# Connectors.net
KiCad netlist of a schematic drawn in Altium Designer
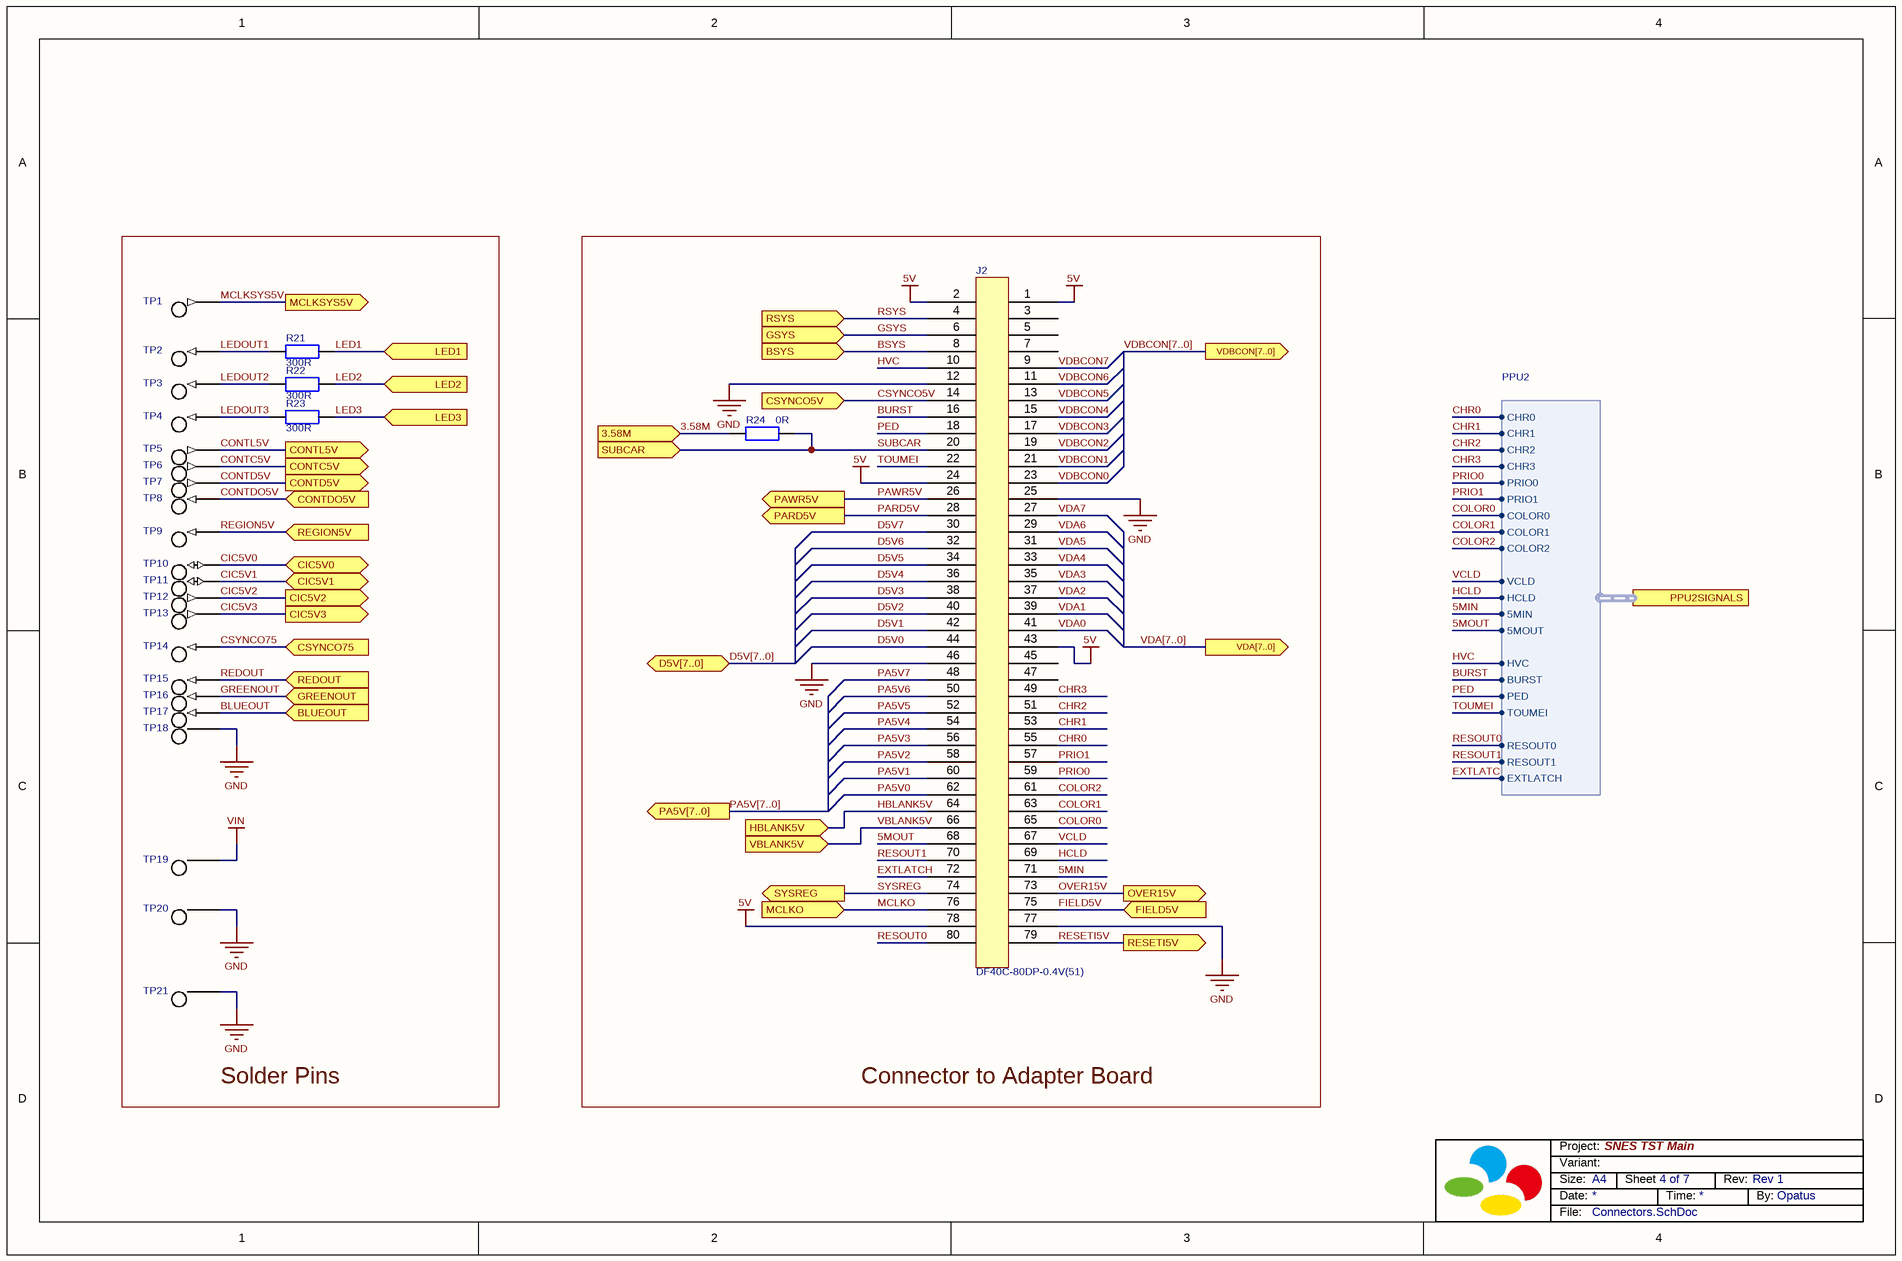
[diagram p0: Connectors.SchDoc]

(export (version "E")
  (design (tool "Eeschema 10.0.6"))
  (components
    (comp (ref "J2")
      (value "DF40C-80DP")
      (footprint "DF40C-80DP")
      (description "80Pole Connector")
      (fields
        (field (name "MANUFACTURER_PART_NUMBER") "DF40C-80DP-0.4V(51)")
        (field (name "MANUFACTURER") "Hirose Connector")
      )
      (libsource (lib "PCB") (part "Conn 80P"))
    )
    (comp (ref "R21")
      (value "300R")
      (footprint "Res_0603_Chip")
      (fields (field (name "TOLERANCE") "±1%") (field (name "Comment") "Resistor 300R 0603 ±1%"))
      (libsource (lib "PCB") (part "R"))
    )
    (comp (ref "R22")
      (value "300R")
      (footprint "Res_0603_Chip")
      (fields (field (name "TOLERANCE") "±1%") (field (name "Comment") "Resistor 300R 0603 ±1%"))
      (libsource (lib "PCB") (part "R"))
    )
    (comp (ref "R23")
      (value "300R")
      (footprint "Res_0603_Chip")
      (fields (field (name "TOLERANCE") "±1%") (field (name "Comment") "Resistor 300R 0603 ±1%"))
      (libsource (lib "PCB") (part "R"))
    )
    (comp (ref "R24")
      (value "0R")
      (footprint "Res_0603_Chip")
      (fields (field (name "TOLERANCE") "±1%") (field (name "Comment") "Resistor 0R 0603 ±1%"))
      (libsource (lib "") (part "R_1"))
    )
    (comp (ref "TP1")
      (value "Pin Connector")
      (footprint "Pin Connector Small")
      (libsource (lib "PCB") (part "Pin Connector"))
    )
    (comp (ref "TP2")
      (value "Pin Connector")
      (footprint "Pin Connector Small")
      (libsource (lib "PCB") (part "Pin Connector"))
    )
    (comp (ref "TP3")
      (value "Pin Connector")
      (footprint "Pin Connector Small")
      (libsource (lib "PCB") (part "Pin Connector"))
    )
    (comp (ref "TP4")
      (value "Pin Connector")
      (footprint "Pin Connector Small")
      (libsource (lib "PCB") (part "Pin Connector"))
    )
    (comp (ref "TP5")
      (value "Pin Connector")
      (footprint "Pin Connector Small")
      (libsource (lib "PCB") (part "Pin Connector"))
    )
    (comp (ref "TP6")
      (value "Pin Connector")
      (footprint "Pin Connector Small")
      (libsource (lib "PCB") (part "Pin Connector"))
    )
    (comp (ref "TP7")
      (value "Pin Connector")
      (footprint "Pin Connector Small")
      (libsource (lib "PCB") (part "Pin Connector"))
    )
    (comp (ref "TP8")
      (value "Pin Connector")
      (footprint "Pin Connector Small")
      (libsource (lib "PCB") (part "Pin Connector"))
    )
    (comp (ref "TP9")
      (value "Pin Connector")
      (footprint "Pin Connector Small")
      (libsource (lib "PCB") (part "Pin Connector"))
    )
    (comp (ref "TP10")
      (value "Pin Connector")
      (footprint "Pin Connector Small")
      (libsource (lib "PCB") (part "Pin Connector"))
    )
    (comp (ref "TP11")
      (value "Pin Connector")
      (footprint "Pin Connector Small")
      (libsource (lib "PCB") (part "Pin Connector"))
    )
    (comp (ref "TP12")
      (value "Pin Connector")
      (footprint "Pin Connector Small")
      (libsource (lib "PCB") (part "Pin Connector"))
    )
    (comp (ref "TP13")
      (value "Pin Connector")
      (footprint "Pin Connector Small")
      (libsource (lib "PCB") (part "Pin Connector"))
    )
    (comp (ref "TP14")
      (value "Pin Connector")
      (footprint "Pin Connector Small")
      (libsource (lib "PCB") (part "Pin Connector"))
    )
    (comp (ref "TP15")
      (value "Pin Connector")
      (footprint "Pin Connector Small")
      (libsource (lib "PCB") (part "Pin Connector"))
    )
    (comp (ref "TP16")
      (value "Pin Connector")
      (footprint "Pin Connector Small")
      (libsource (lib "PCB") (part "Pin Connector"))
    )
    (comp (ref "TP17")
      (value "Pin Connector")
      (footprint "Pin Connector Small")
      (libsource (lib "PCB") (part "Pin Connector"))
    )
    (comp (ref "TP18")
      (value "Pin Connector")
      (footprint "Pin Connector Small")
      (libsource (lib "PCB") (part "Pin Connector"))
    )
    (comp (ref "TP19")
      (value "Pin Connector")
      (footprint "Pin Connector Small")
      (libsource (lib "PCB") (part "Pin Connector"))
    )
    (comp (ref "TP20")
      (value "Pin Connector")
      (footprint "Pin Connector Small")
      (libsource (lib "PCB") (part "Pin Connector"))
    )
    (comp (ref "TP21")
      (value "Pin Connector")
      (footprint "Pin Connector Small")
      (libsource (lib "PCB") (part "Pin Connector"))
    )
  )
  (nets
    (net (code "2") (name "/3.58M") (class "Default") (node (ref "R24") (pin "2") (pintype "passive")))
    (net (code "3") (name "/5MIN") (class "Default") (node (ref "J2") (pin "71") (pintype "passive")))
    (net (code "4") (name "/5MOUT") (class "Default") (node (ref "J2") (pin "68") (pintype "passive")))
    (net (code "5") (name "/BLUEOUT") (class "Default")
      (node (ref "TP17") (pin "1") (pinfunction "0_1") (pintype "output"))
    )
    (net (code "6") (name "/BSYS") (class "Default") (node (ref "J2") (pin "8") (pintype "passive")))
    (net (code "7") (name "/BURST") (class "Default") (node (ref "J2") (pin "16") (pintype "passive")))
    (net (code "8") (name "/CHR0") (class "Default") (node (ref "J2") (pin "55") (pintype "passive")))
    (net (code "9") (name "/CHR1") (class "Default") (node (ref "J2") (pin "53") (pintype "passive")))
    (net (code "10") (name "/CHR2") (class "Default") (node (ref "J2") (pin "51") (pintype "passive")))
    (net (code "11") (name "/CHR3") (class "Default") (node (ref "J2") (pin "49") (pintype "passive")))
    (net (code "12") (name "/CIC5V0") (class "Default")
      (node (ref "TP10") (pin "1") (pinfunction "0_1") (pintype "output"))
    )
    (net (code "13") (name "/CIC5V1") (class "Default")
      (node (ref "TP11") (pin "1") (pinfunction "0_1") (pintype "output"))
    )
    (net (code "14") (name "/CIC5V2") (class "Default")
      (node (ref "TP12") (pin "1") (pinfunction "0_1") (pintype "output"))
    )
    (net (code "15") (name "/CIC5V3") (class "Default")
      (node (ref "TP13") (pin "1") (pinfunction "0_1") (pintype "output"))
    )
    (net (code "16") (name "/COLOR0") (class "Default") (node (ref "J2") (pin "65") (pintype "passive")))
    (net (code "17") (name "/COLOR1") (class "Default") (node (ref "J2") (pin "63") (pintype "passive")))
    (net (code "18") (name "/COLOR2") (class "Default") (node (ref "J2") (pin "61") (pintype "passive")))
    (net (code "19") (name "/CONTC5V") (class "Default")
      (node (ref "TP6") (pin "1") (pinfunction "0_1") (pintype "output"))
    )
    (net (code "20") (name "/CONTD5V") (class "Default")
      (node (ref "TP7") (pin "1") (pinfunction "0_1") (pintype "output"))
    )
    (net (code "21") (name "/CONTDO5V") (class "Default")
      (node (ref "TP8") (pin "1") (pinfunction "0_1") (pintype "output"))
    )
    (net (code "22") (name "/CONTL5V") (class "Default")
      (node (ref "TP5") (pin "1") (pinfunction "0_1") (pintype "output"))
    )
    (net (code "23") (name "/CSYNCO5V") (class "Default") (node (ref "J2") (pin "14") (pintype "passive")))
    (net (code "24") (name "/CSYNCO75") (class "Default")
      (node (ref "TP14") (pin "1") (pinfunction "0_1") (pintype "output"))
    )
    (net (code "25") (name "/D5V0") (class "Default") (node (ref "J2") (pin "44") (pintype "passive")))
    (net (code "26") (name "/D5V1") (class "Default") (node (ref "J2") (pin "42") (pintype "passive")))
    (net (code "27") (name "/D5V2") (class "Default") (node (ref "J2") (pin "40") (pintype "passive")))
    (net (code "28") (name "/D5V3") (class "Default") (node (ref "J2") (pin "38") (pintype "passive")))
    (net (code "29") (name "/D5V4") (class "Default") (node (ref "J2") (pin "36") (pintype "passive")))
    (net (code "30") (name "/D5V5") (class "Default") (node (ref "J2") (pin "34") (pintype "passive")))
    (net (code "31") (name "/D5V6") (class "Default") (node (ref "J2") (pin "32") (pintype "passive")))
    (net (code "32") (name "/D5V7") (class "Default") (node (ref "J2") (pin "30") (pintype "passive")))
    (net (code "34") (name "/EXTLATCH") (class "Default") (node (ref "J2") (pin "72") (pintype "passive")))
    (net (code "35") (name "/FIELD5V") (class "Default") (node (ref "J2") (pin "75") (pintype "passive")))
    (net (code "36") (name "/GREENOUT") (class "Default")
      (node (ref "TP16") (pin "1") (pinfunction "0_1") (pintype "output"))
    )
    (net (code "37") (name "/GSYS") (class "Default") (node (ref "J2") (pin "6") (pintype "passive")))
    (net (code "38") (name "/HBLANK5V") (class "Default") (node (ref "J2") (pin "64") (pintype "passive")))
    (net (code "39") (name "/HCLD") (class "Default") (node (ref "J2") (pin "69") (pintype "passive")))
    (net (code "40") (name "/HVC") (class "Default") (node (ref "J2") (pin "10") (pintype "passive")))
    (net (code "41") (name "/LED1") (class "Default") (node (ref "R21") (pin "2") (pintype "passive")))
    (net (code "42") (name "/LED2") (class "Default") (node (ref "R22") (pin "2") (pintype "passive")))
    (net (code "43") (name "/LED3") (class "Default") (node (ref "R23") (pin "2") (pintype "passive")))
    (net (code "44") (name "/LEDOUT1") (class "Default")
      (node (ref "R21") (pin "1") (pintype "passive"))
      (node (ref "TP2") (pin "1") (pinfunction "0_1") (pintype "output"))
    )
    (net (code "45") (name "/LEDOUT2") (class "Default")
      (node (ref "R22") (pin "1") (pintype "passive"))
      (node (ref "TP3") (pin "1") (pinfunction "0_1") (pintype "output"))
    )
    (net (code "46") (name "/LEDOUT3") (class "Default")
      (node (ref "R23") (pin "1") (pintype "passive"))
      (node (ref "TP4") (pin "1") (pinfunction "0_1") (pintype "output"))
    )
    (net (code "47") (name "/MCLKO") (class "Default") (node (ref "J2") (pin "76") (pintype "passive")))
    (net (code "48") (name "/MCLKSYS5V") (class "Default")
      (node (ref "TP1") (pin "1") (pinfunction "0_1") (pintype "output"))
    )
    (net (code "49") (name "/OVER15V") (class "Default") (node (ref "J2") (pin "73") (pintype "passive")))
    (net (code "50") (name "/PA5V0") (class "Default") (node (ref "J2") (pin "62") (pintype "passive")))
    (net (code "51") (name "/PA5V1") (class "Default") (node (ref "J2") (pin "60") (pintype "passive")))
    (net (code "52") (name "/PA5V2") (class "Default") (node (ref "J2") (pin "58") (pintype "passive")))
    (net (code "53") (name "/PA5V3") (class "Default") (node (ref "J2") (pin "56") (pintype "passive")))
    (net (code "54") (name "/PA5V4") (class "Default") (node (ref "J2") (pin "54") (pintype "passive")))
    (net (code "55") (name "/PA5V5") (class "Default") (node (ref "J2") (pin "52") (pintype "passive")))
    (net (code "56") (name "/PA5V6") (class "Default") (node (ref "J2") (pin "50") (pintype "passive")))
    (net (code "57") (name "/PA5V7") (class "Default") (node (ref "J2") (pin "48") (pintype "passive")))
    (net (code "59") (name "/PARD5V") (class "Default") (node (ref "J2") (pin "28") (pintype "passive")))
    (net (code "60") (name "/PAWR5V") (class "Default") (node (ref "J2") (pin "26") (pintype "passive")))
    (net (code "61") (name "/PED") (class "Default") (node (ref "J2") (pin "18") (pintype "passive")))
    (net (code "62") (name "/PRIO0") (class "Default") (node (ref "J2") (pin "59") (pintype "passive")))
    (net (code "63") (name "/PRIO1") (class "Default") (node (ref "J2") (pin "57") (pintype "passive")))
    (net (code "64") (name "/REDOUT") (class "Default")
      (node (ref "TP15") (pin "1") (pinfunction "0_1") (pintype "output"))
    )
    (net (code "65") (name "/REGION5V") (class "Default")
      (node (ref "TP9") (pin "1") (pinfunction "0_1") (pintype "output"))
    )
    (net (code "66") (name "/RESETI5V") (class "Default") (node (ref "J2") (pin "79") (pintype "passive")))
    (net (code "67") (name "/RESOUT0") (class "Default") (node (ref "J2") (pin "80") (pintype "passive")))
    (net (code "68") (name "/RESOUT1") (class "Default") (node (ref "J2") (pin "70") (pintype "passive")))
    (net (code "69") (name "/RSYS") (class "Default") (node (ref "J2") (pin "4") (pintype "passive")))
    (net (code "70") (name "/SUBCAR") (class "Default")
      (node (ref "J2") (pin "20") (pintype "passive"))
      (node (ref "R24") (pin "1") (pintype "passive"))
    )
    (net (code "71") (name "/SYSREG") (class "Default") (node (ref "J2") (pin "74") (pintype "passive")))
    (net (code "72") (name "/TOUMEI") (class "Default") (node (ref "J2") (pin "22") (pintype "passive")))
    (net (code "73") (name "/VBLANK5V") (class "Default") (node (ref "J2") (pin "66") (pintype "passive")))
    (net (code "74") (name "/VCLD") (class "Default") (node (ref "J2") (pin "67") (pintype "passive")))
    (net (code "75") (name "/VDA0") (class "Default") (node (ref "J2") (pin "41") (pintype "passive")))
    (net (code "76") (name "/VDA1") (class "Default") (node (ref "J2") (pin "39") (pintype "passive")))
    (net (code "77") (name "/VDA2") (class "Default") (node (ref "J2") (pin "37") (pintype "passive")))
    (net (code "78") (name "/VDA3") (class "Default") (node (ref "J2") (pin "35") (pintype "passive")))
    (net (code "79") (name "/VDA4") (class "Default") (node (ref "J2") (pin "33") (pintype "passive")))
    (net (code "80") (name "/VDA5") (class "Default") (node (ref "J2") (pin "31") (pintype "passive")))
    (net (code "81") (name "/VDA6") (class "Default") (node (ref "J2") (pin "29") (pintype "passive")))
    (net (code "82") (name "/VDA7") (class "Default") (node (ref "J2") (pin "27") (pintype "passive")))
    (net (code "84") (name "/VDBCON0") (class "Default") (node (ref "J2") (pin "23") (pintype "passive")))
    (net (code "85") (name "/VDBCON1") (class "Default") (node (ref "J2") (pin "21") (pintype "passive")))
    (net (code "86") (name "/VDBCON2") (class "Default") (node (ref "J2") (pin "19") (pintype "passive")))
    (net (code "87") (name "/VDBCON3") (class "Default") (node (ref "J2") (pin "17") (pintype "passive")))
    (net (code "88") (name "/VDBCON4") (class "Default") (node (ref "J2") (pin "15") (pintype "passive")))
    (net (code "89") (name "/VDBCON5") (class "Default") (node (ref "J2") (pin "13") (pintype "passive")))
    (net (code "90") (name "/VDBCON6") (class "Default") (node (ref "J2") (pin "11") (pintype "passive")))
    (net (code "91") (name "/VDBCON7") (class "Default") (node (ref "J2") (pin "9") (pintype "passive")))
    (net (code "94") (name "5V") (class "Default")
      (node (ref "J2") (pin "1") (pintype "passive"))
      (node (ref "J2") (pin "2") (pintype "passive"))
      (node (ref "J2") (pin "24") (pintype "passive"))
      (node (ref "J2") (pin "43") (pintype "passive"))
      (node (ref "J2") (pin "78") (pintype "passive"))
    )
    (net (code "95") (name "GND") (class "Default")
      (node (ref "J2") (pin "12") (pintype "passive"))
      (node (ref "J2") (pin "25") (pintype "passive"))
      (node (ref "J2") (pin "46") (pintype "passive"))
      (node (ref "J2") (pin "77") (pintype "passive"))
      (node (ref "TP18") (pin "1") (pinfunction "0_1") (pintype "output"))
      (node (ref "TP20") (pin "1") (pinfunction "0_1") (pintype "output"))
      (node (ref "TP21") (pin "1") (pinfunction "0_1") (pintype "output"))
    )
    (net (code "96") (name "VIN") (class "Default")
      (node (ref "TP19") (pin "1") (pinfunction "0_1") (pintype "output"))
    )
    (net (code "97") (name "unconnected-(J2-Pad3)") (class "Default")
      (node (ref "J2") (pin "3") (pintype "passive"))
    )
    (net (code "98") (name "unconnected-(J2-Pad5)") (class "Default")
      (node (ref "J2") (pin "5") (pintype "passive"))
    )
    (net (code "99") (name "unconnected-(J2-Pad7)") (class "Default")
      (node (ref "J2") (pin "7") (pintype "passive"))
    )
    (net (code "100") (name "unconnected-(J2-Pad45)") (class "Default")
      (node (ref "J2") (pin "45") (pintype "passive"))
    )
    (net (code "101") (name "unconnected-(J2-Pad47)") (class "Default")
      (node (ref "J2") (pin "47") (pintype "passive"))
    )
  )
)
